# manual-button.net
KiCad netlist of a schematic drawn in EAGLE
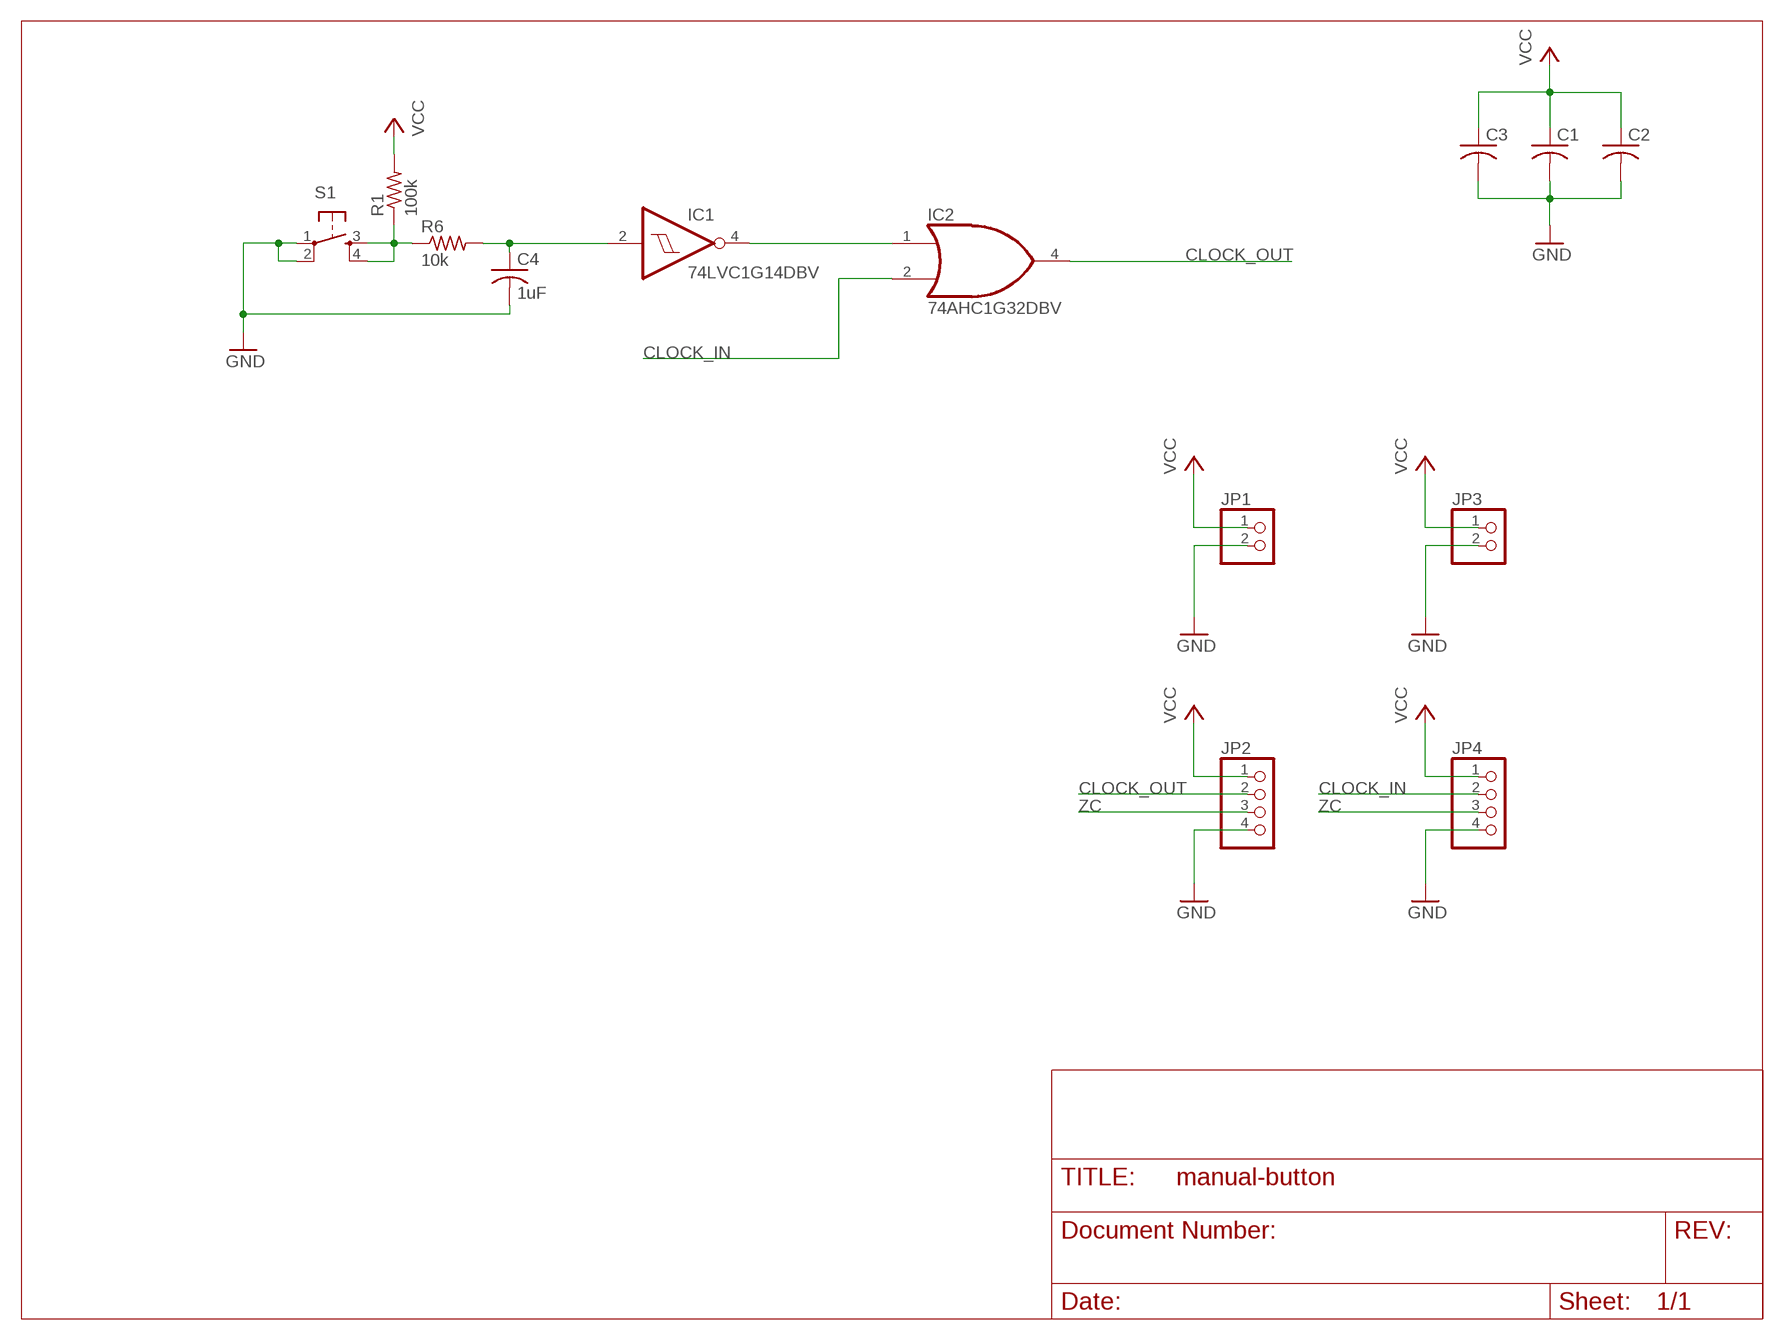
[diagram p0: schematic, sheet 1]

(export (version "E")
  (design (tool "Eeschema 10.0.6"))
  (components
    (comp (ref "C1")
      (value "C-USC0603K")
      (footprint "eagle-import:C0603K")
      (libsource (lib "eagle-import") (part "C-USC0603K"))
    )
    (comp (ref "C2")
      (value "C-USC0603K")
      (footprint "eagle-import:C0603K")
      (libsource (lib "eagle-import") (part "C-USC0603K"))
    )
    (comp (ref "C3")
      (value "C-USC0603K")
      (footprint "eagle-import:C0603K")
      (libsource (lib "eagle-import") (part "C-USC0603K"))
    )
    (comp (ref "C4")
      (value "1uF")
      (footprint "eagle-import:C0603K")
      (libsource (lib "eagle-import") (part "C-USC0603K"))
    )
    (comp (ref "IC1")
      (value "74LVC1G14DBV")
      (footprint "eagle-import:SOT23-5")
      (libsource (lib "eagle-import") (part "741G14DBVLVC"))
    )
    (comp (ref "IC2")
      (value "74AHC1G32DBV")
      (footprint "eagle-import:SOT23-5")
      (libsource (lib "eagle-import") (part "741G32DBVAHC"))
    )
    (comp (ref "JP1")
      (value "PINHD-1X2")
      (footprint "eagle-import:1X02")
      (libsource (lib "eagle-import") (part "PINHD-1X2"))
    )
    (comp (ref "JP2")
      (value "PINHD-1X4")
      (footprint "eagle-import:1X04")
      (libsource (lib "eagle-import") (part "PINHD-1X4"))
    )
    (comp (ref "JP3")
      (value "PINHD-1X2")
      (footprint "eagle-import:1X02")
      (libsource (lib "eagle-import") (part "PINHD-1X2"))
    )
    (comp (ref "JP4")
      (value "PINHD-1X4")
      (footprint "eagle-import:1X04")
      (libsource (lib "eagle-import") (part "PINHD-1X4"))
    )
    (comp (ref "R1")
      (value "100k")
      (footprint "eagle-import:R0603")
      (libsource (lib "eagle-import") (part "R-US_R0603"))
    )
    (comp (ref "R6")
      (value "10k")
      (footprint "eagle-import:R0603")
      (libsource (lib "eagle-import") (part "R-US_R0603"))
    )
    (comp (ref "S1")
      (value "TAC_SWITCHPTH")
      (footprint "eagle-import:TACTILE-PTH")
      (libsource (lib "eagle-import") (part "TAC_SWITCHPTH"))
    )
  )
  (nets
    (net (code "1") (name "/CLOCK_IN") (class "Default")
      (node (ref "IC2") (pin "2") (pinfunction "I1_2") (pintype "input"))
      (node (ref "JP4") (pin "2") (pinfunction "2_2") (pintype "passive"))
    )
    (net (code "2") (name "/CLOCK_OUT") (class "Default")
      (node (ref "IC2") (pin "4") (pinfunction "O_4") (pintype "output"))
      (node (ref "JP2") (pin "2") (pinfunction "2_2") (pintype "passive"))
    )
    (net (code "3") (name "/ZC") (class "Default")
      (node (ref "JP2") (pin "3") (pinfunction "3_3") (pintype "passive"))
      (node (ref "JP4") (pin "3") (pinfunction "3_3") (pintype "passive"))
    )
    (net (code "4") (name "GND") (class "Default")
      (node (ref "C1") (pin "2") (pinfunction "2_2") (pintype "passive"))
      (node (ref "C2") (pin "2") (pinfunction "2_2") (pintype "passive"))
      (node (ref "C3") (pin "2") (pinfunction "2_2") (pintype "passive"))
      (node (ref "C4") (pin "2") (pinfunction "2_2") (pintype "passive"))
      (node (ref "JP1") (pin "2") (pinfunction "2_2") (pintype "passive"))
      (node (ref "JP2") (pin "4") (pinfunction "4_4") (pintype "passive"))
      (node (ref "JP3") (pin "2") (pinfunction "2_2") (pintype "passive"))
      (node (ref "JP4") (pin "4") (pinfunction "4_4") (pintype "passive"))
      (node (ref "S1") (pin "1") (pinfunction "1_1") (pintype "passive"))
      (node (ref "S1") (pin "2") (pinfunction "2_2") (pintype "passive"))
    )
    (net (code "5") (name "Net-(IC1A-I)") (class "Default")
      (node (ref "C4") (pin "1") (pinfunction "1_1") (pintype "passive"))
      (node (ref "IC1") (pin "2") (pinfunction "I_2") (pintype "input"))
      (node (ref "R6") (pin "2") (pinfunction "2_2") (pintype "passive"))
    )
    (net (code "6") (name "Net-(IC1A-O)") (class "Default")
      (node (ref "IC1") (pin "4") (pinfunction "O_4") (pintype "output"))
      (node (ref "IC2") (pin "1") (pinfunction "I0_1") (pintype "input"))
    )
    (net (code "7") (name "Net-(R1-Pad1)") (class "Default")
      (node (ref "R1") (pin "1") (pinfunction "1_1") (pintype "passive"))
      (node (ref "R6") (pin "1") (pinfunction "1_1") (pintype "passive"))
      (node (ref "S1") (pin "3") (pinfunction "3_3") (pintype "passive"))
      (node (ref "S1") (pin "4") (pinfunction "4_4") (pintype "passive"))
    )
    (net (code "8") (name "VCC") (class "Default")
      (node (ref "C1") (pin "1") (pinfunction "1_1") (pintype "passive"))
      (node (ref "C2") (pin "1") (pinfunction "1_1") (pintype "passive"))
      (node (ref "C3") (pin "1") (pinfunction "1_1") (pintype "passive"))
      (node (ref "JP1") (pin "1") (pinfunction "1_1") (pintype "passive"))
      (node (ref "JP2") (pin "1") (pinfunction "1_1") (pintype "passive"))
      (node (ref "JP3") (pin "1") (pinfunction "1_1") (pintype "passive"))
      (node (ref "JP4") (pin "1") (pinfunction "1_1") (pintype "passive"))
      (node (ref "R1") (pin "2") (pinfunction "2_2") (pintype "passive"))
    )
  )
)
